# EDU_High-Speed-Design_CPU_SPI_I2C.net
KiCad netlist of a schematic drawn in Altium Designer
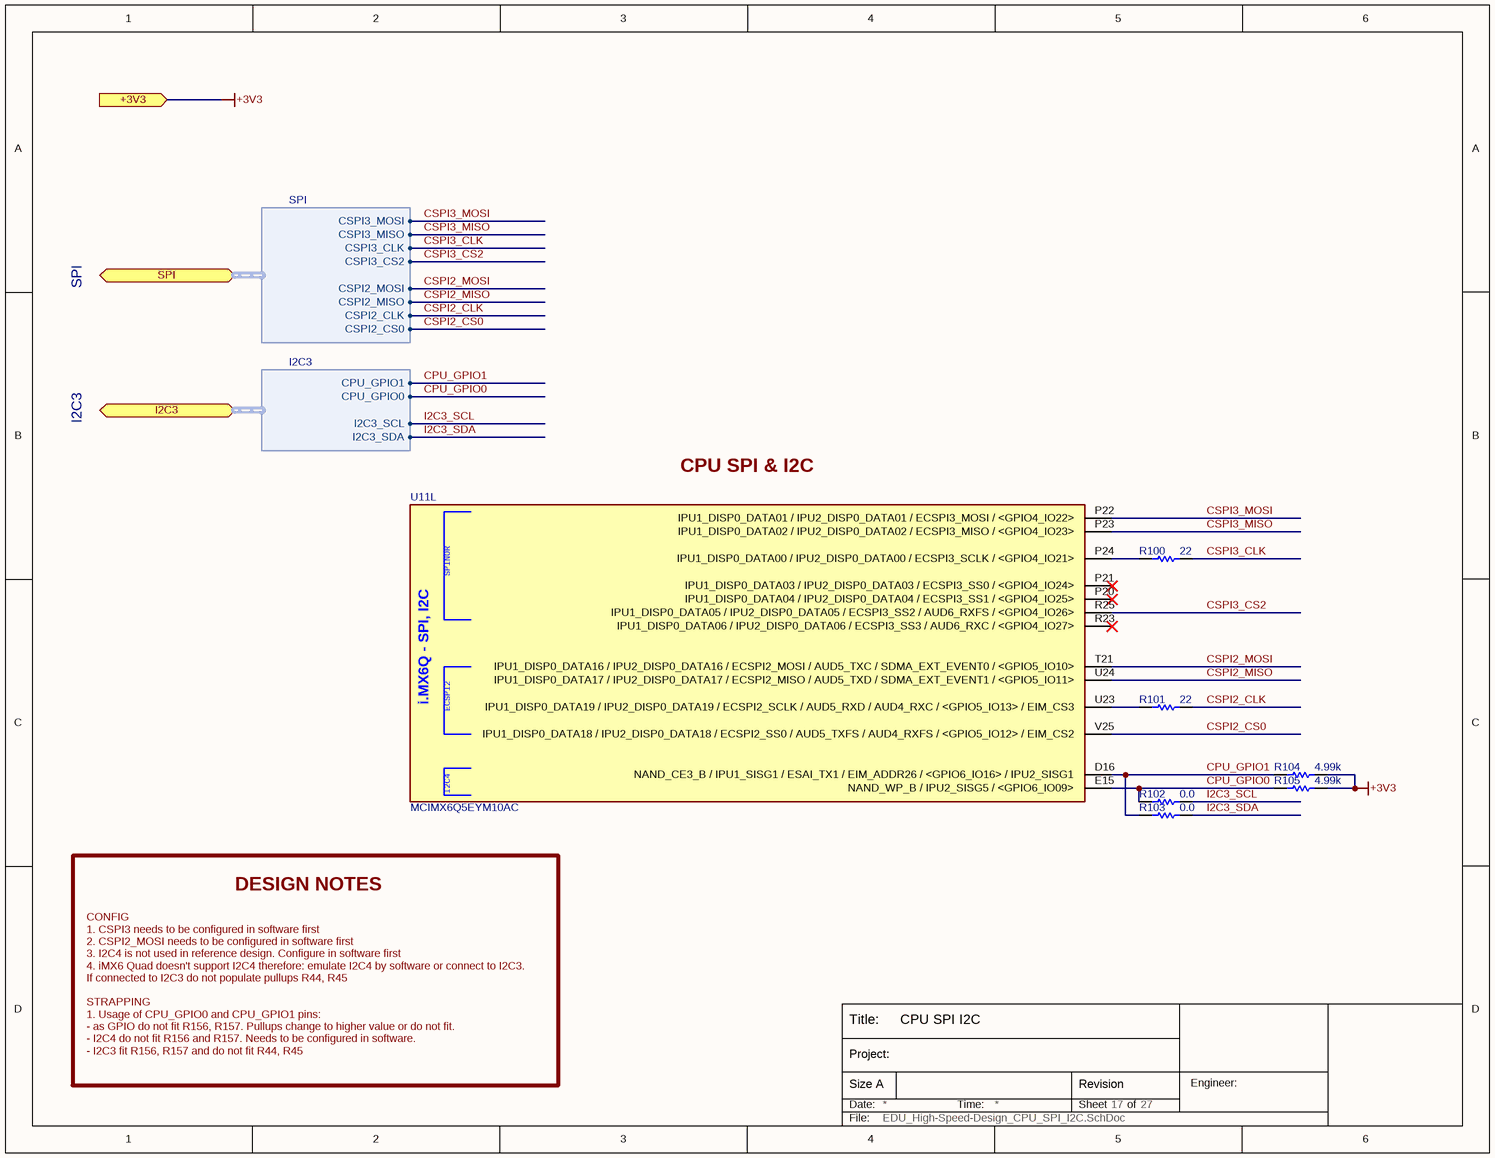
[diagram p0: EDU_High-Speed-Design_CPU_SPI_I2C.SchDoc]

(export (version "E")
  (design (tool "Eeschema 10.0.6"))
  (components
    (comp (ref "R100")
      (value "22")
      (footprint "R0402")
      (description "RES 22.0 OHM 1/16W 1% 0402 SMD")
      (libsource (lib "EDU_High-Speed-Design") (part "RC0402FR-0722RL"))
    )
    (comp (ref "R101")
      (value "22")
      (footprint "R0402")
      (description "RES 22.0 OHM 1/16W 1% 0402 SMD")
      (libsource (lib "EDU_High-Speed-Design") (part "RC0402FR-0722RL"))
    )
    (comp (ref "R102")
      (value "0.0")
      (footprint "R0402")
      (description "RES 0.0 OHM 1/16W 0402 SMD")
      (libsource (lib "EDU_High-Speed-Design") (part "RC0402JR-070RL"))
    )
    (comp (ref "R103")
      (value "0.0")
      (footprint "R0402")
      (description "RES 0.0 OHM 1/16W 0402 SMD")
      (libsource (lib "EDU_High-Speed-Design") (part "RC0402JR-070RL"))
    )
    (comp (ref "R104")
      (value "4.99k")
      (footprint "R0402")
      (description "RES TF 4.99K OHM 1% 1/16W 0402")
      (libsource (lib "EDU_High-Speed-Design") (part "RMCF0402FT4K99"))
    )
    (comp (ref "R105")
      (value "4.99k")
      (footprint "R0402")
      (description "RES TF 4.99K OHM 1% 1/16W 0402")
      (libsource (lib "EDU_High-Speed-Design") (part "RMCF0402FT4K99"))
    )
    (comp (ref "U11")
      (value "MCIMX6Q5EYM10AC")
      (footprint "MCIMX6Q5EYM10AC")
      (description "IC MCU 32BIT ARM QUAD 624FCBGA")
      (libsource (lib "EDU_High-Speed-Design") (part "MCIMX6Q5EYM10AC"))
    )
  )
  (nets
    (net (code "3") (name "+3V3") (class "Default")
      (node (ref "R104") (pin "1") (pinfunction "1_1") (pintype "passive"))
      (node (ref "R105") (pin "1") (pinfunction "1_1") (pintype "passive"))
    )
    (net (code "4") (name "/CPU_GPIO0") (class "Default")
      (node (ref "R102") (pin "2") (pinfunction "2_2") (pintype "passive"))
      (node (ref "R105") (pin "2") (pinfunction "2_2") (pintype "passive"))
      (node (ref "U11") (pin "E15") (pinfunction "NAND_WP_B_/_IPU2_SISG5_/_<GPIO6_IO09>_E15") (pintype "passive"))
    )
    (net (code "5") (name "/CPU_GPIO1") (class "Default")
      (node (ref "R103") (pin "2") (pinfunction "2_2") (pintype "passive"))
      (node (ref "R104") (pin "2") (pinfunction "2_2") (pintype "passive"))
      (node (ref "U11") (pin "D16") (pinfunction "NAND_CE3_B_/_IPU1_SISG1_/_ESAI_TX1_/_EIM_ADDR26_/_<GPIO6_IO16>_/_IPU2_SISG1_D16") (pintype "passive"))
    )
    (net (code "6") (name "/CSPI2_CLK") (class "Default")
      (node (ref "R101") (pin "1") (pinfunction "1_1") (pintype "passive"))
    )
    (net (code "7") (name "/CSPI2_CS0") (class "Default")
      (node (ref "U11") (pin "V25") (pinfunction "IPU1_DISP0_DATA18_/_IPU2_DISP0_DATA18_/_ECSPI2_SS0_/_AUD5_TXFS_/_AUD4_RXFS_/_<GPIO5_IO12>_/_EIM_CS2_V25") (pintype "passive"))
    )
    (net (code "8") (name "/CSPI2_MISO") (class "Default")
      (node (ref "U11") (pin "U24") (pinfunction "IPU1_DISP0_DATA17_/_IPU2_DISP0_DATA17_/_ECSPI2_MISO_/_AUD5_TXD_/_SDMA_EXT_EVENT1_/_<GPIO5_IO11>_U24") (pintype "passive"))
    )
    (net (code "9") (name "/CSPI2_MOSI") (class "Default")
      (node (ref "U11") (pin "T21") (pinfunction "IPU1_DISP0_DATA16_/_IPU2_DISP0_DATA16_/_ECSPI2_MOSI_/_AUD5_TXC_/_SDMA_EXT_EVENT0_/_<GPIO5_IO10>_T21") (pintype "passive"))
    )
    (net (code "10") (name "/CSPI3_CLK") (class "Default")
      (node (ref "R100") (pin "1") (pinfunction "1_1") (pintype "passive"))
    )
    (net (code "11") (name "/CSPI3_CS2") (class "Default")
      (node (ref "U11") (pin "R25") (pinfunction "IPU1_DISP0_DATA05_/_IPU2_DISP0_DATA05_/_ECSPI3_SS2_/_AUD6_RXFS_/_<GPIO4_IO26>_R25") (pintype "passive"))
    )
    (net (code "12") (name "/CSPI3_MISO") (class "Default")
      (node (ref "U11") (pin "P23") (pinfunction "IPU1_DISP0_DATA02_/_IPU2_DISP0_DATA02_/_ECSPI3_MISO_/_<GPIO4_IO23>_P23") (pintype "passive"))
    )
    (net (code "13") (name "/CSPI3_MOSI") (class "Default")
      (node (ref "U11") (pin "P22") (pinfunction "IPU1_DISP0_DATA01_/_IPU2_DISP0_DATA01_/_ECSPI3_MOSI_/_<GPIO4_IO22>_P22") (pintype "passive"))
    )
    (net (code "14") (name "/I2C3_SCL") (class "Default")
      (node (ref "R102") (pin "1") (pinfunction "1_1") (pintype "passive"))
    )
    (net (code "15") (name "/I2C3_SDA") (class "Default")
      (node (ref "R103") (pin "1") (pinfunction "1_1") (pintype "passive"))
    )
    (net (code "18") (name "Net-(U11L-IPU1_DISP0_DATA00_{slash}_IPU2_DISP0_DATA00_{slash}_ECSPI3_SCLK_{slash}_<GPIO4_IO21>)") (class "Default")
      (node (ref "R100") (pin "2") (pinfunction "2_2") (pintype "passive"))
      (node (ref "U11") (pin "P24") (pinfunction "IPU1_DISP0_DATA00_/_IPU2_DISP0_DATA00_/_ECSPI3_SCLK_/_<GPIO4_IO21>_P24") (pintype "passive"))
    )
    (net (code "19") (name "Net-(U11L-IPU1_DISP0_DATA19_{slash}_IPU2_DISP0_DATA19_{slash}_ECSPI2_SCLK_{slash}_AUD5_RXD_{slash}_AUD4_RXC_{slash}_<GPIO5_IO13>_{slash}_EIM_CS3)") (class "Default")
      (node (ref "R101") (pin "2") (pinfunction "2_2") (pintype "passive"))
      (node (ref "U11") (pin "U23") (pinfunction "IPU1_DISP0_DATA19_/_IPU2_DISP0_DATA19_/_ECSPI2_SCLK_/_AUD5_RXD_/_AUD4_RXC_/_<GPIO5_IO13>_/_EIM_CS3_U23") (pintype "passive"))
    )
    (net (code "20") (name "unconnected-(U11L-IPU1_DISP0_DATA03_{slash}_IPU2_DISP0_DATA03_{slash}_ECSPI3_SS0_{slash}_<GPIO4_IO24>-PadP21)") (class "Default")
      (node (ref "U11") (pin "P21") (pinfunction "IPU1_DISP0_DATA03_/_IPU2_DISP0_DATA03_/_ECSPI3_SS0_/_<GPIO4_IO24>_P21") (pintype "passive+no_connect"))
    )
    (net (code "21") (name "unconnected-(U11L-IPU1_DISP0_DATA04_{slash}_IPU2_DISP0_DATA04_{slash}_ECSPI3_SS1_{slash}_<GPIO4_IO25>-PadP20)") (class "Default")
      (node (ref "U11") (pin "P20") (pinfunction "IPU1_DISP0_DATA04_/_IPU2_DISP0_DATA04_/_ECSPI3_SS1_/_<GPIO4_IO25>_P20") (pintype "passive+no_connect"))
    )
    (net (code "22") (name "unconnected-(U11L-IPU1_DISP0_DATA06_{slash}_IPU2_DISP0_DATA06_{slash}_ECSPI3_SS3_{slash}_AUD6_RXC_{slash}_<GPIO4_IO27>-PadR23)") (class "Default")
      (node (ref "U11") (pin "R23") (pinfunction "IPU1_DISP0_DATA06_/_IPU2_DISP0_DATA06_/_ECSPI3_SS3_/_AUD6_RXC_/_<GPIO4_IO27>_R23") (pintype "passive+no_connect"))
    )
  )
)
